# OpenBLC_TPS61230.net
KiCad netlist of a schematic drawn in Altium Designer
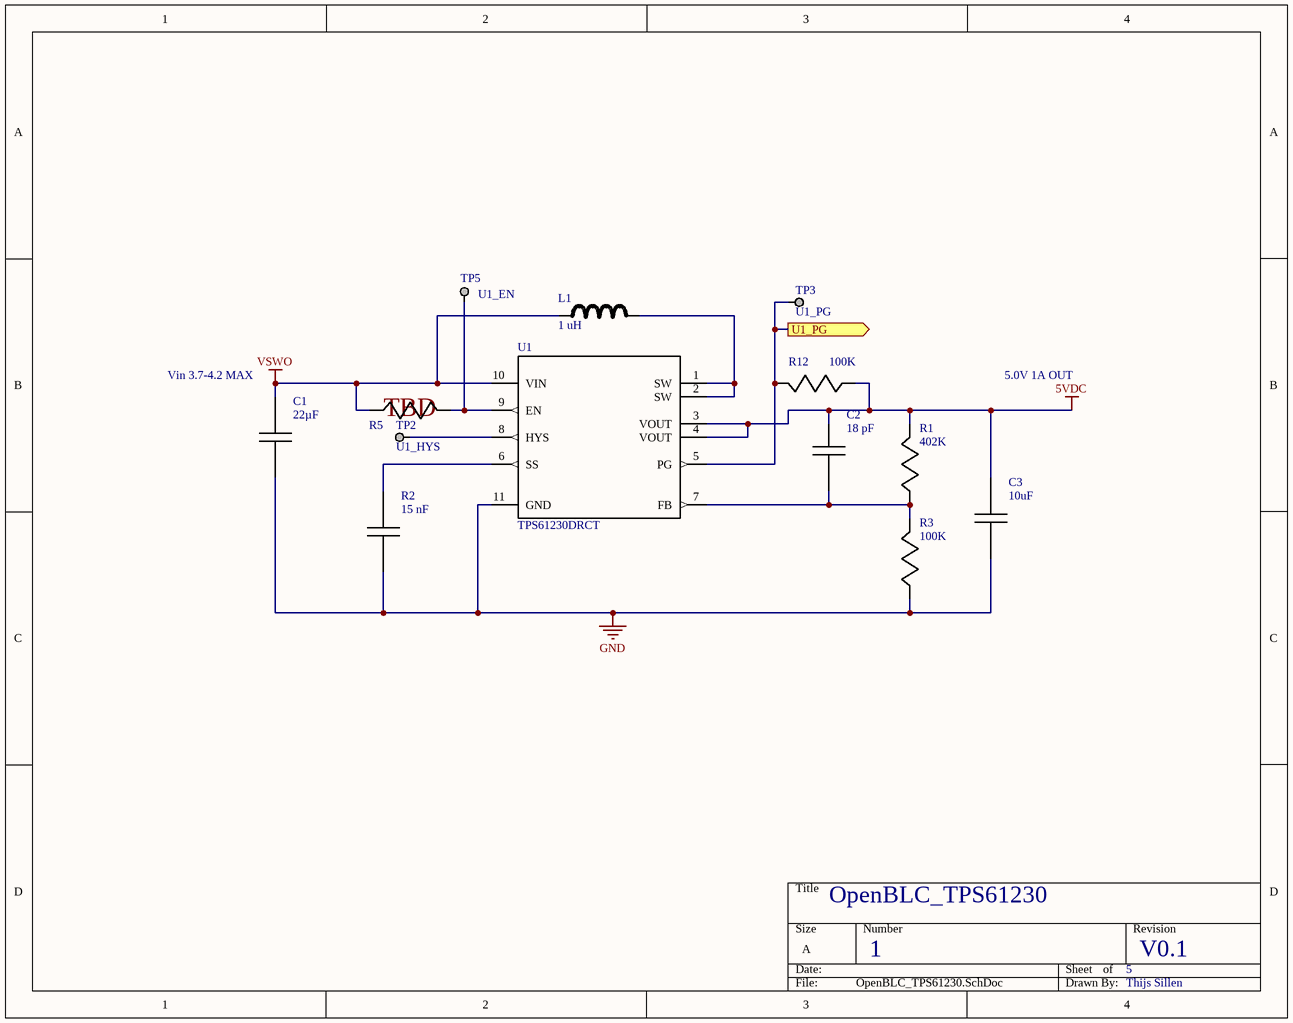
[diagram p0: OpenBLC_TPS61230.SchDoc]

(export (version "E")
  (design (tool "Eeschema 10.0.6"))
  (components
    (comp (ref "C1")
      (value "C2012X5R0J226M125AC")
      (footprint "0805_CAP")
      (description "CAP CER 22UF 6.3V 20% X5R 0805")
      (fields
        (field (name "MANUFACTURER") "TDK Corporation")
        (field (name "TOLERANCE") "±20%")
        (field (name "CAPACITANCE") "22µF")
      )
      (libsource (lib "Schlib1") (part "C2012X5R0J226M125AC"))
    )
    (comp (ref "C2")
      (value "C0603C180J5GACTU")
      (footprint "0603_CAP")
      (description "Meerlaagse keramische condensatoren MLCC - SMD/SMT 50volts 18pF C0G 5%")
      (fields (field (name "MANUFACTURER") "Kemet") (field (name "CAPACITEIT") "18 pF"))
      (libsource (lib "Schlib1") (part "C0603C180J5GACTU"))
    )
    (comp (ref "C3")
      (value "GRM21BR61A106KE19L")
      (footprint "0805_CAP")
      (description "MURATA - GRM21BR61A106KE19L - CAPACITOR, CERA, 10UF, 10%, 10V, 10%, SMD")
      (fields (field (name "MANUFACTURER") "MURATA") (field (name "CAPACITANCE") "10uF"))
      (libsource (lib "Schlib1") (part "GRM21BR61A106KE19L"))
    )
    (comp (ref "L1")
      (value "SRU1028-1R0Y")
      (footprint "SRU1028")
      (description "Vaste smoorspoelen 1uH 30% SMD 1028")
      (fields (field (name "MANUFACTURER") "Bourns") (field (name "INDUCTANTIE") "1 uH"))
      (libsource (lib "Schlib1") (part "SRU1028-1R0Y"))
    )
    (comp (ref "R1")
      (value "CRCW0402402KFKED")
      (footprint "0402_RES")
      (description "VISHAY DRALORIC - CRCW0402402KFKED - RESISTOR, 0402, 402K, 1%")
      (fields (field (name "MANUFACTURER") "VISHAY DRALORIC") (field (name "RESISTANCE") "402K"))
      (libsource (lib "Schlib1") (part "CRCW0402402KFKED"))
    )
    (comp (ref "R2")
      (value "GRM155R71C153KA01D")
      (footprint "0402_CAP")
      (description "Meerlaagse keramische condensatoren MLCC - SMD/SMT 0402 0.015uF 16volts X7R 10%")
      (fields (field (name "MANUFACTURER") "Murata Electronics") (field (name "CAPACITEIT") "15 nF"))
      (libsource (lib "Schlib1") (part "GRM155R71C153KA01D"))
    )
    (comp (ref "R3")
      (value "CRCW0402100KFKEDHP")
      (footprint "0402_RES")
      (description "VISHAY DRALORIC - CRCW0402100KFKEDHP - RESISTOR, POWER, 100K, 0.125W, 1%")
      (fields (field (name "MANUFACTURER") "VISHAY DRALORIC") (field (name "RESISTANCE") "100K"))
      (libsource (lib "Schlib1") (part "CRCW0402100KFKEDHP"))
    )
    (comp (ref "R5") (value "0805_RES") (footprint "0805_RES") (libsource (lib "Schlib1") (part "0805_RES")))
    (comp (ref "R12")
      (value "CRCW0402100KFKEDHP")
      (footprint "0402_RES")
      (description "VISHAY DRALORIC - CRCW0402100KFKEDHP - RESISTOR, POWER, 100K, 0.125W, 1%")
      (fields (field (name "MANUFACTURER") "VISHAY DRALORIC") (field (name "RESISTANCE") "100K"))
      (libsource (lib "Schlib1") (part "CRCW0402100KFKEDHP"))
    )
    (comp (ref "TP2")
      (value "U1_HYS")
      (footprint "Via_TP")
      (description "TESTPOINT SCOPE GRABBER")
      (fields
        (field (name "MANUFACTURER PART NUMBER") "5010")
        (field (name "MANUFACTURER") "Keystone Electronics")
      )
      (libsource (lib "vh_altium_library") (part "TESTPOINT"))
    )
    (comp (ref "TP3")
      (value "U1_PG")
      (footprint "Via_TP")
      (description "TESTPOINT SCOPE GRABBER")
      (fields
        (field (name "MANUFACTURER PART NUMBER") "5010")
        (field (name "MANUFACTURER") "Keystone Electronics")
      )
      (libsource (lib "vh_altium_library") (part "TESTPOINT"))
    )
    (comp (ref "TP5")
      (value "U1_EN")
      (footprint "Via_TP")
      (description "TESTPOINT SCOPE GRABBER")
      (fields
        (field (name "MANUFACTURER PART NUMBER") "5010")
        (field (name "MANUFACTURER") "Keystone Electronics")
      )
      (libsource (lib "vh_altium_library") (part "TESTPOINT"))
    )
    (comp (ref "U1")
      (value "TPS61230DRCT")
      (footprint "TPS61230DRCR")
      (fields
        (field (name "MANUFACTURER") "Texas Instruments")
        (field (name "MANUFACTURER PART NUMBER") "TPS61230DRCT")
      )
      (libsource (lib "Schlib1") (part "TPS61230DRCT"))
    )
  )
  (nets
    (net (code "1") (name "/U1_PG") (class "Default")
      (node (ref "R12") (pin "1") (pinfunction "1_1") (pintype "passive"))
      (node (ref "TP3") (pin "1") (pinfunction "1_1") (pintype "passive"))
      (node (ref "U1") (pin "5") (pinfunction "PG_5") (pintype "output"))
    )
    (net (code "2") (name "5VDC") (class "Default")
      (node (ref "C2") (pin "1") (pinfunction "1_1") (pintype "passive"))
      (node (ref "C3") (pin "1") (pinfunction "1_1") (pintype "passive"))
      (node (ref "R1") (pin "1") (pinfunction "1_1") (pintype "passive"))
      (node (ref "R12") (pin "2") (pinfunction "2_2") (pintype "passive"))
      (node (ref "U1") (pin "3") (pinfunction "VOUT_3") (pintype "power_in"))
      (node (ref "U1") (pin "4") (pinfunction "VOUT_4") (pintype "power_in"))
    )
    (net (code "3") (name "GND") (class "Default")
      (node (ref "C1") (pin "2") (pinfunction "2_2") (pintype "passive"))
      (node (ref "C3") (pin "2") (pinfunction "2_2") (pintype "passive"))
      (node (ref "R2") (pin "2") (pinfunction "2_2") (pintype "passive"))
      (node (ref "R3") (pin "2") (pinfunction "2_2") (pintype "passive"))
      (node (ref "U1") (pin "11") (pinfunction "GND_11") (pintype "power_in"))
    )
    (net (code "4") (name "Net-(L1-Pad1)") (class "Default")
      (node (ref "L1") (pin "1") (pinfunction "1_1") (pintype "passive"))
      (node (ref "U1") (pin "1") (pinfunction "SW_1") (pintype "power_in"))
      (node (ref "U1") (pin "2") (pinfunction "SW_2") (pintype "power_in"))
    )
    (net (code "5") (name "Net-(U1-EN)") (class "Default")
      (node (ref "R5") (pin "1") (pinfunction "1_1") (pintype "passive"))
      (node (ref "TP5") (pin "1") (pinfunction "1_1") (pintype "passive"))
      (node (ref "U1") (pin "9") (pinfunction "EN_9") (pintype "output"))
    )
    (net (code "6") (name "Net-(U1-FB)") (class "Default")
      (node (ref "C2") (pin "2") (pinfunction "2_2") (pintype "passive"))
      (node (ref "R1") (pin "2") (pinfunction "2_2") (pintype "passive"))
      (node (ref "R3") (pin "1") (pinfunction "1_1") (pintype "passive"))
      (node (ref "U1") (pin "7") (pinfunction "FB_7") (pintype "output"))
    )
    (net (code "7") (name "Net-(U1-HYS)") (class "Default")
      (node (ref "TP2") (pin "1") (pinfunction "1_1") (pintype "passive"))
      (node (ref "U1") (pin "8") (pinfunction "HYS_8") (pintype "output"))
    )
    (net (code "8") (name "Net-(U1-SS)") (class "Default")
      (node (ref "R2") (pin "1") (pinfunction "1_1") (pintype "passive"))
      (node (ref "U1") (pin "6") (pinfunction "SS_6") (pintype "output"))
    )
    (net (code "9") (name "VSWO") (class "Default")
      (node (ref "C1") (pin "1") (pinfunction "1_1") (pintype "passive"))
      (node (ref "L1") (pin "2") (pinfunction "2_2") (pintype "passive"))
      (node (ref "R5") (pin "2") (pinfunction "2_2") (pintype "passive"))
      (node (ref "U1") (pin "10") (pinfunction "VIN_10") (pintype "power_in"))
    )
  )
)
